# ProPrj_hid-remapper-v2_2026-05-31.net
KiCad netlist of a schematic drawn in EasyEDA Pro
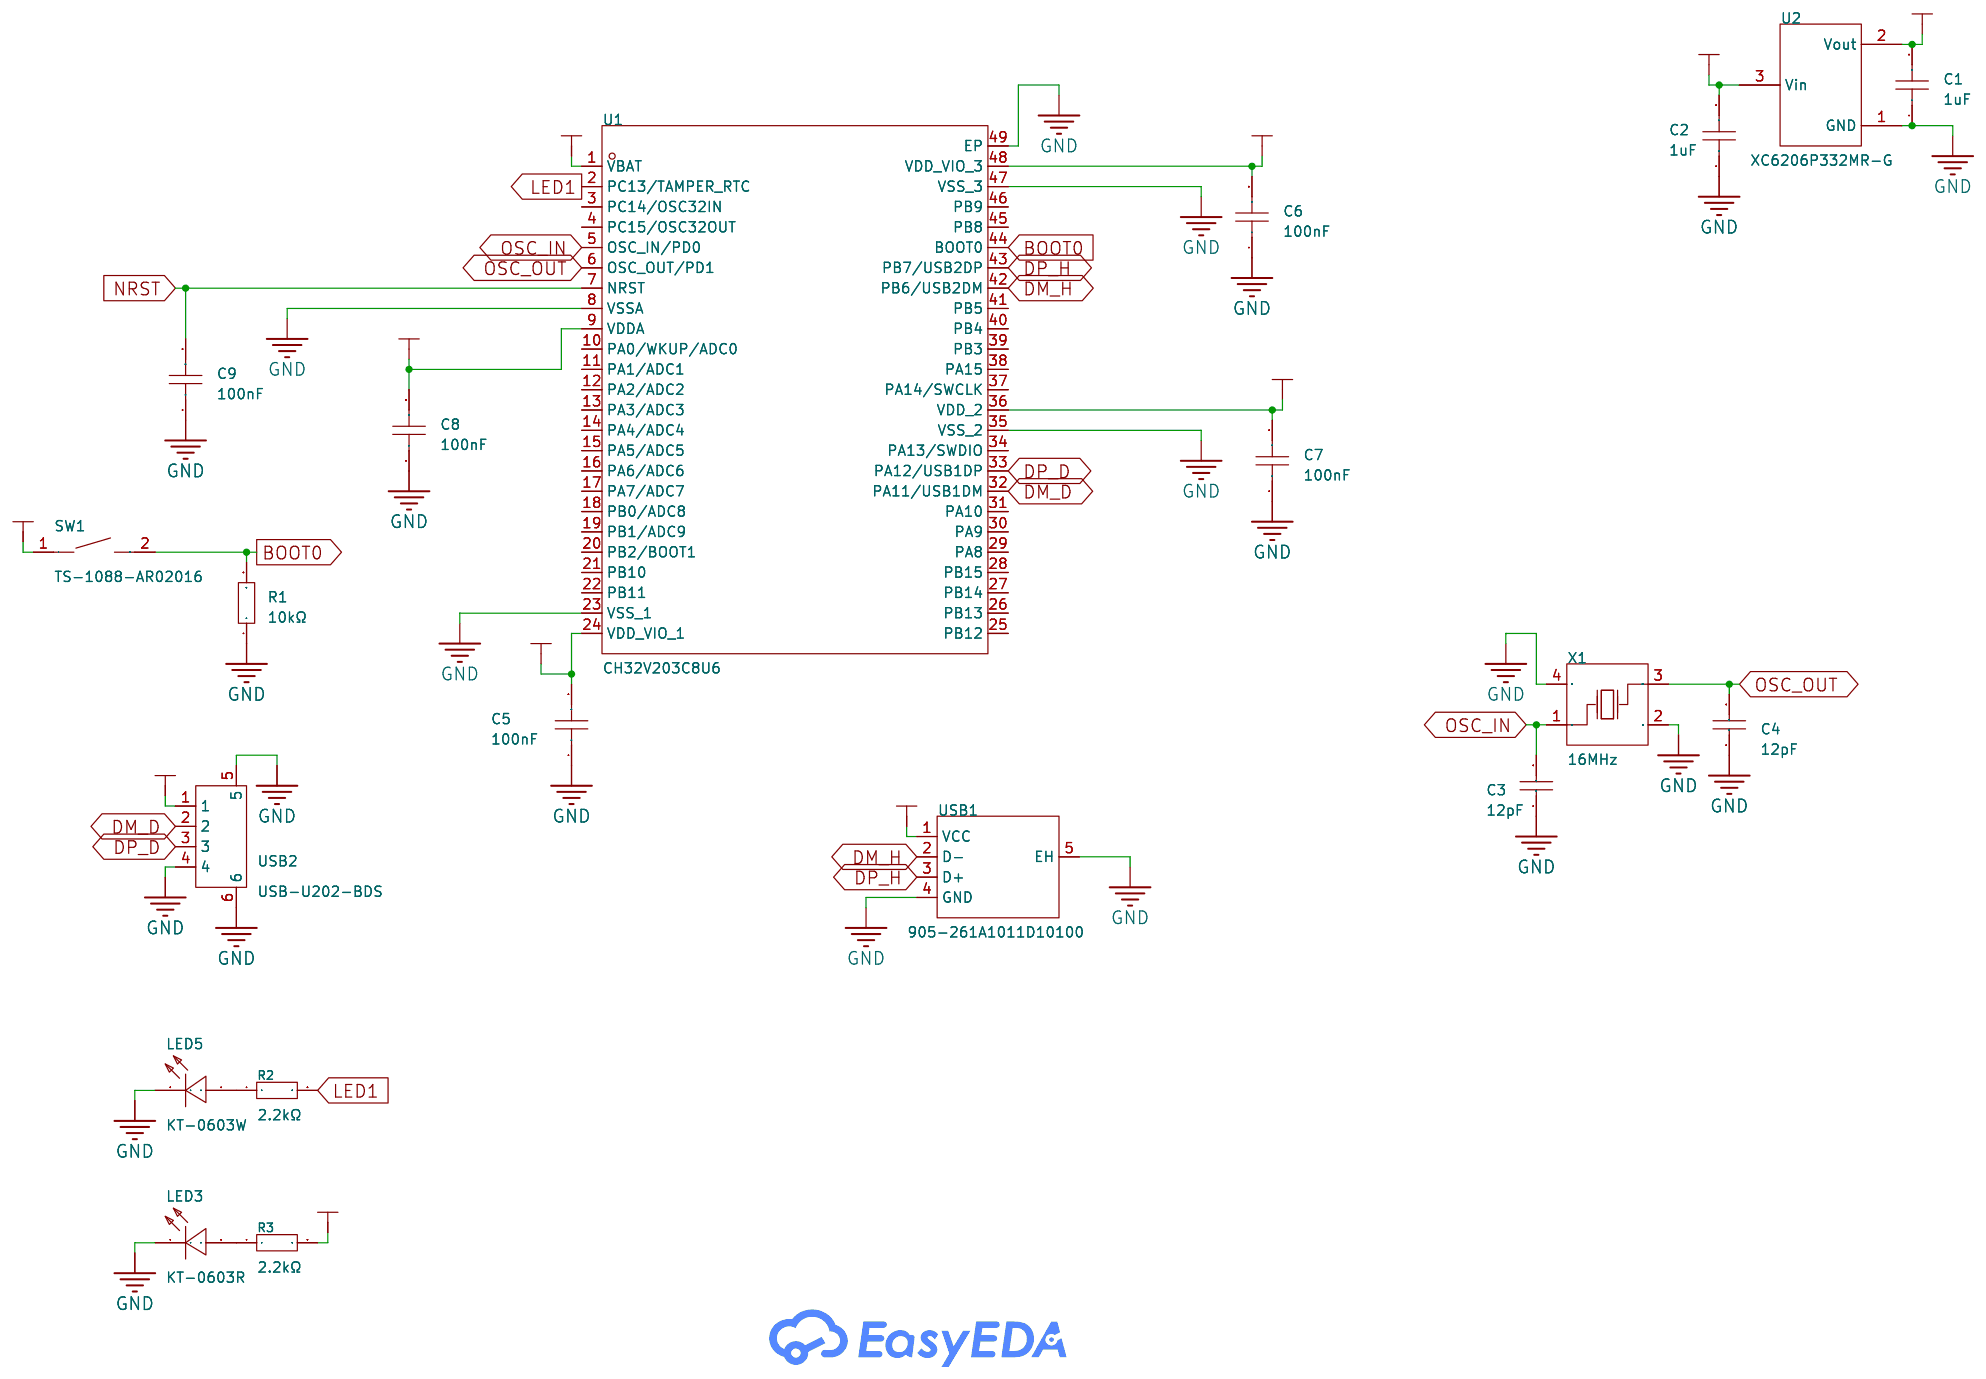
[diagram p0: schematic sheet]

(export (version "E")
  (design (tool "Eeschema 10.0.6"))
  (components
    (comp (ref "C1")
      (value "1uF")
      (footprint "easyedapro:C0402")
      (description "Capacitance:1uF Tolerance:±10% Tolerance:±10% Voltage Rating:25V Temperature Coefficient:X5R")
      (fields
        (field (name "Manufacturer Part") "CL05A105KA5NQNC")
        (field (name "Manufacturer") "SAMSUNG(三星)")
      )
      (libsource (lib "easyedapro") (part "CL05A105KA5NQNC"))
    )
    (comp (ref "C2")
      (value "1uF")
      (footprint "easyedapro:C0402")
      (description "Capacitance:1uF Tolerance:±10% Tolerance:±10% Voltage Rating:25V Temperature Coefficient:X5R")
      (fields
        (field (name "Manufacturer Part") "CL05A105KA5NQNC")
        (field (name "Manufacturer") "SAMSUNG(三星)")
      )
      (libsource (lib "easyedapro") (part "CL05A105KA5NQNC"))
    )
    (comp (ref "C3")
      (value "12pF")
      (footprint "easyedapro:C0402")
      (description "Capacitance:12pF Tolerance:±5% Tolerance:±5% Voltage Rating:50V Temperature Coefficient:C0G")
      (fields (field (name "Manufacturer Part") "0402CG120J500NT") (field (name "Manufacturer") "FH(风华)"))
      (libsource (lib "easyedapro") (part "0402CG120J500NT"))
    )
    (comp (ref "C4")
      (value "12pF")
      (footprint "easyedapro:C0402")
      (description "Capacitance:12pF Tolerance:±5% Tolerance:±5% Voltage Rating:50V Temperature Coefficient:C0G")
      (fields (field (name "Manufacturer Part") "0402CG120J500NT") (field (name "Manufacturer") "FH(风华)"))
      (libsource (lib "easyedapro") (part "0402CG120J500NT"))
    )
    (comp (ref "C5")
      (value "100nF")
      (footprint "easyedapro:C0402")
      (description "Capacitance:100nF Tolerance:±10% Tolerance:±10% Voltage Rating:16V Temperature Coefficient:X7R")
      (fields
        (field (name "Manufacturer Part") "CL05B104KO5NNNC")
        (field (name "Manufacturer") "SAMSUNG(三星)")
      )
      (libsource (lib "easyedapro") (part "CL05B104KO5NNNC"))
    )
    (comp (ref "C6")
      (value "100nF")
      (footprint "easyedapro:C0402")
      (description "Capacitance:100nF Tolerance:±10% Tolerance:±10% Voltage Rating:16V Temperature Coefficient:X7R")
      (fields
        (field (name "Manufacturer Part") "CL05B104KO5NNNC")
        (field (name "Manufacturer") "SAMSUNG(三星)")
      )
      (libsource (lib "easyedapro") (part "CL05B104KO5NNNC"))
    )
    (comp (ref "C7")
      (value "100nF")
      (footprint "easyedapro:C0402")
      (description "Capacitance:100nF Tolerance:±10% Tolerance:±10% Voltage Rating:16V Temperature Coefficient:X7R")
      (fields
        (field (name "Manufacturer Part") "CL05B104KO5NNNC")
        (field (name "Manufacturer") "SAMSUNG(三星)")
      )
      (libsource (lib "easyedapro") (part "CL05B104KO5NNNC"))
    )
    (comp (ref "C8")
      (value "100nF")
      (footprint "easyedapro:C0402")
      (description "Capacitance:100nF Tolerance:±10% Tolerance:±10% Voltage Rating:16V Temperature Coefficient:X7R")
      (fields
        (field (name "Manufacturer Part") "CL05B104KO5NNNC")
        (field (name "Manufacturer") "SAMSUNG(三星)")
      )
      (libsource (lib "easyedapro") (part "CL05B104KO5NNNC"))
    )
    (comp (ref "C9")
      (value "100nF")
      (footprint "easyedapro:C0402")
      (description "Capacitance:100nF Tolerance:±10% Tolerance:±10% Voltage Rating:16V Temperature Coefficient:X7R")
      (fields
        (field (name "Manufacturer Part") "CL05B104KO5NNNC")
        (field (name "Manufacturer") "SAMSUNG(三星)")
      )
      (libsource (lib "easyedapro") (part "CL05B104KO5NNNC"))
    )
    (comp (ref "LED3")
      (value "KT-0603R")
      (footprint "easyedapro:LED0603-RD")
      (fields (field (name "Manufacturer") "KENTO"))
      (libsource (lib "easyedapro") (part "KT-0603R"))
    )
    (comp (ref "LED5")
      (value "KT-0603W")
      (footprint "easyedapro:LED0603-R-RD_WHITE")
      (fields (field (name "Manufacturer") "KENTO"))
      (libsource (lib "easyedapro") (part "0603White light_C2290"))
    )
    (comp (ref "R1")
      (value "10kΩ")
      (footprint "easyedapro:R0402")
      (fields
        (field (name "Manufacturer Part") "0402WGF1002TCE")
        (field (name "Manufacturer") "UNI-ROYAL(厚声)")
      )
      (libsource (lib "easyedapro") (part "0402WGF1002TCE"))
    )
    (comp (ref "R2")
      (value "2.2kΩ")
      (footprint "easyedapro:R0402")
      (fields
        (field (name "Manufacturer Part") "0402WGF2201TCE")
        (field (name "Manufacturer") "UNI-ROYAL(厚声)")
      )
      (libsource (lib "easyedapro") (part "0402WGF2201TCE"))
    )
    (comp (ref "R3")
      (value "2.2kΩ")
      (footprint "easyedapro:R0402")
      (fields
        (field (name "Manufacturer Part") "0402WGF2201TCE")
        (field (name "Manufacturer") "UNI-ROYAL(厚声)")
      )
      (libsource (lib "easyedapro") (part "0402WGF2201TCE"))
    )
    (comp (ref "SW1")
      (value "TS-1088-AR02016")
      (footprint "easyedapro:SW-SMD_L3.9-W3.0-P4.45")
      (fields (field (name "Manufacturer") "XUNPU(讯普)"))
      (libsource (lib "easyedapro") (part "TS-1088-AR02016"))
    )
    (comp (ref "U1")
      (value "CH32V203C8U6")
      (footprint "easyedapro:TQFN-48_L7.0-W7.0-P0.50-BL-EP5.5")
      (fields (field (name "Manufacturer") "WCH(南京沁恒)"))
      (libsource (lib "easyedapro") (part "CH32V203C8U6"))
    )
    (comp (ref "U2")
      (value "XC6206P332MR-G")
      (footprint "easyedapro:SOT-23-3_L2.9-W1.6-P1.90-LS2.8-BR")
      (fields (field (name "Manufacturer") "TOREX(特瑞仕)"))
      (libsource (lib "easyedapro") (part "XC6206P332MR"))
    )
    (comp (ref "USB1")
      (value "905-261A1011D10100")
      (footprint "easyedapro:USB-A-TH_JTJ-USB-AF-13")
      (fields (field (name "Manufacturer") "精拓金"))
      (libsource (lib "easyedapro") (part "C42614"))
    )
    (comp (ref "USB2")
      (value "USB-U202-BDS")
      (footprint "easyedapro:USB_USB-U202-BDS")
      (fields (field (name "Manufacturer") "HANBO(汉博)"))
      (libsource (lib "easyedapro") (part "USB-U202-BDS"))
    )
    (comp (ref "X1")
      (value "16MHz")
      (footprint "easyedapro:OSC-SMD_4P-L3.2-W2.5-BL")
      (fields (field (name "Manufacturer Part") "X322516MLB4SI") (field (name "Manufacturer") "YXC(扬兴晶振)"))
      (libsource (lib "easyedapro") (part "X322516MLB4SI"))
    )
  )
  (nets
    (net (code "1") (name "3V3") (class "Default")
      (node (ref "C1") (pin "2") (pinfunction "2_2") (pintype "unspecified"))
      (node (ref "C5") (pin "2") (pinfunction "2_2") (pintype "unspecified"))
      (node (ref "C6") (pin "2") (pinfunction "2_2") (pintype "unspecified"))
      (node (ref "C7") (pin "2") (pinfunction "2_2") (pintype "unspecified"))
      (node (ref "C8") (pin "2") (pinfunction "2_2") (pintype "unspecified"))
      (node (ref "R3") (pin "2") (pinfunction "2_2") (pintype "input"))
      (node (ref "SW1") (pin "1") (pinfunction "1_1") (pintype "unspecified"))
      (node (ref "U1") (pin "1") (pinfunction "VBAT_1") (pintype "unspecified"))
      (node (ref "U1") (pin "24") (pinfunction "VDD_VIO_1_24") (pintype "unspecified"))
      (node (ref "U1") (pin "36") (pinfunction "VDD_2_36") (pintype "unspecified"))
      (node (ref "U1") (pin "48") (pinfunction "VDD_VIO_3_48") (pintype "unspecified"))
      (node (ref "U1") (pin "9") (pinfunction "VDDA_9") (pintype "unspecified"))
      (node (ref "U2") (pin "2") (pinfunction "Vout_2") (pintype "unspecified"))
    )
    (net (code "2") (name "BOOT0") (class "Default")
      (node (ref "R1") (pin "2") (pinfunction "2_2") (pintype "input"))
      (node (ref "SW1") (pin "2") (pinfunction "2_2") (pintype "unspecified"))
      (node (ref "U1") (pin "44") (pinfunction "BOOT0_44") (pintype "unspecified"))
    )
    (net (code "3") (name "DM_D") (class "Default")
      (node (ref "U1") (pin "32") (pinfunction "PA11/USB1DM_32") (pintype "unspecified"))
      (node (ref "USB2") (pin "2") (pinfunction "2_2") (pintype "unspecified"))
    )
    (net (code "4") (name "DM_H") (class "Default")
      (node (ref "U1") (pin "42") (pinfunction "PB6/USB2DM_42") (pintype "unspecified"))
      (node (ref "USB1") (pin "2") (pinfunction "D-_2") (pintype "input"))
    )
    (net (code "5") (name "DP_D") (class "Default")
      (node (ref "U1") (pin "33") (pinfunction "PA12/USB1DP_33") (pintype "unspecified"))
      (node (ref "USB2") (pin "3") (pinfunction "3_3") (pintype "unspecified"))
    )
    (net (code "6") (name "DP_H") (class "Default")
      (node (ref "U1") (pin "43") (pinfunction "PB7/USB2DP_43") (pintype "unspecified"))
      (node (ref "USB1") (pin "3") (pinfunction "D+_3") (pintype "input"))
    )
    (net (code "7") (name "GND") (class "Default")
      (node (ref "C1") (pin "1") (pinfunction "1_1") (pintype "unspecified"))
      (node (ref "C2") (pin "1") (pinfunction "1_1") (pintype "unspecified"))
      (node (ref "C3") (pin "1") (pinfunction "1_1") (pintype "input"))
      (node (ref "C4") (pin "1") (pinfunction "1_1") (pintype "input"))
      (node (ref "C5") (pin "1") (pinfunction "1_1") (pintype "unspecified"))
      (node (ref "C6") (pin "1") (pinfunction "1_1") (pintype "unspecified"))
      (node (ref "C7") (pin "1") (pinfunction "1_1") (pintype "unspecified"))
      (node (ref "C8") (pin "1") (pinfunction "1_1") (pintype "unspecified"))
      (node (ref "C9") (pin "1") (pinfunction "1_1") (pintype "unspecified"))
      (node (ref "LED3") (pin "1") (pinfunction "K_1") (pintype "unspecified"))
      (node (ref "LED5") (pin "2") (pinfunction "K_2") (pintype "unspecified"))
      (node (ref "R1") (pin "1") (pinfunction "1_1") (pintype "input"))
      (node (ref "U1") (pin "23") (pinfunction "VSS_1_23") (pintype "unspecified"))
      (node (ref "U1") (pin "35") (pinfunction "VSS_2_35") (pintype "unspecified"))
      (node (ref "U1") (pin "47") (pinfunction "VSS_3_47") (pintype "unspecified"))
      (node (ref "U1") (pin "49") (pinfunction "EP_49") (pintype "unspecified"))
      (node (ref "U1") (pin "8") (pinfunction "VSSA_8") (pintype "unspecified"))
      (node (ref "U2") (pin "1") (pinfunction "GND_1") (pintype "unspecified"))
      (node (ref "USB1") (pin "4") (pinfunction "GND_4") (pintype "input"))
      (node (ref "USB1") (pin "5") (pinfunction "EH_5") (pintype "unspecified"))
      (node (ref "USB2") (pin "4") (pinfunction "4_4") (pintype "unspecified"))
      (node (ref "USB2") (pin "5") (pinfunction "5_5") (pintype "unspecified"))
      (node (ref "USB2") (pin "6") (pinfunction "6_6") (pintype "unspecified"))
      (node (ref "X1") (pin "2") (pinfunction "GND_2") (pintype "unspecified"))
      (node (ref "X1") (pin "4") (pinfunction "GND_4") (pintype "unspecified"))
    )
    (net (code "8") (name "LED1") (class "Default")
      (node (ref "R2") (pin "2") (pinfunction "2_2") (pintype "input"))
      (node (ref "U1") (pin "2") (pinfunction "PC13/TAMPER_RTC_2") (pintype "unspecified"))
    )
    (net (code "9") (name "NRST") (class "Default")
      (node (ref "C9") (pin "2") (pinfunction "2_2") (pintype "unspecified"))
      (node (ref "U1") (pin "7") (pinfunction "NRST_7") (pintype "unspecified"))
    )
    (net (code "10") (name "Net-(LED3-A)") (class "Default")
      (node (ref "LED3") (pin "2") (pinfunction "A_2") (pintype "unspecified"))
      (node (ref "R3") (pin "1") (pinfunction "1_1") (pintype "input"))
    )
    (net (code "11") (name "Net-(LED5-A)") (class "Default")
      (node (ref "LED5") (pin "1") (pinfunction "A_1") (pintype "unspecified"))
      (node (ref "R2") (pin "1") (pinfunction "1_1") (pintype "input"))
    )
    (net (code "12") (name "OSC_IN") (class "Default")
      (node (ref "C3") (pin "2") (pinfunction "2_2") (pintype "input"))
      (node (ref "U1") (pin "5") (pinfunction "OSC_IN/PD0_5") (pintype "unspecified"))
      (node (ref "X1") (pin "1") (pinfunction "OSC1_1") (pintype "unspecified"))
    )
    (net (code "13") (name "OSC_OUT") (class "Default")
      (node (ref "C4") (pin "2") (pinfunction "2_2") (pintype "input"))
      (node (ref "U1") (pin "6") (pinfunction "OSC_OUT/PD1_6") (pintype "unspecified"))
      (node (ref "X1") (pin "3") (pinfunction "OSC2_3") (pintype "unspecified"))
    )
    (net (code "14") (name "VBUS") (class "Default")
      (node (ref "C2") (pin "2") (pinfunction "2_2") (pintype "unspecified"))
      (node (ref "U2") (pin "3") (pinfunction "Vin_3") (pintype "unspecified"))
      (node (ref "USB1") (pin "1") (pinfunction "VCC_1") (pintype "input"))
      (node (ref "USB2") (pin "1") (pinfunction "1_1") (pintype "unspecified"))
    )
    (net (code "15") (name "unconnected-(U1-PA0{slash}WKUP{slash}ADC0-Pad10)") (class "Default")
      (node (ref "U1") (pin "10") (pinfunction "PA0/WKUP/ADC0_10") (pintype "unspecified"))
    )
    (net (code "16") (name "unconnected-(U1-PA1{slash}ADC1-Pad11)") (class "Default")
      (node (ref "U1") (pin "11") (pinfunction "PA1/ADC1_11") (pintype "unspecified"))
    )
    (net (code "17") (name "unconnected-(U1-PA2{slash}ADC2-Pad12)") (class "Default")
      (node (ref "U1") (pin "12") (pinfunction "PA2/ADC2_12") (pintype "unspecified"))
    )
    (net (code "18") (name "unconnected-(U1-PA3{slash}ADC3-Pad13)") (class "Default")
      (node (ref "U1") (pin "13") (pinfunction "PA3/ADC3_13") (pintype "unspecified"))
    )
    (net (code "19") (name "unconnected-(U1-PA4{slash}ADC4-Pad14)") (class "Default")
      (node (ref "U1") (pin "14") (pinfunction "PA4/ADC4_14") (pintype "unspecified"))
    )
    (net (code "20") (name "unconnected-(U1-PA5{slash}ADC5-Pad15)") (class "Default")
      (node (ref "U1") (pin "15") (pinfunction "PA5/ADC5_15") (pintype "unspecified"))
    )
    (net (code "21") (name "unconnected-(U1-PA6{slash}ADC6-Pad16)") (class "Default")
      (node (ref "U1") (pin "16") (pinfunction "PA6/ADC6_16") (pintype "unspecified"))
    )
    (net (code "22") (name "unconnected-(U1-PA7{slash}ADC7-Pad17)") (class "Default")
      (node (ref "U1") (pin "17") (pinfunction "PA7/ADC7_17") (pintype "unspecified"))
    )
    (net (code "23") (name "unconnected-(U1-PA8-Pad29)") (class "Default")
      (node (ref "U1") (pin "29") (pinfunction "PA8_29") (pintype "unspecified"))
    )
    (net (code "24") (name "unconnected-(U1-PA9-Pad30)") (class "Default")
      (node (ref "U1") (pin "30") (pinfunction "PA9_30") (pintype "unspecified"))
    )
    (net (code "25") (name "unconnected-(U1-PA10-Pad31)") (class "Default")
      (node (ref "U1") (pin "31") (pinfunction "PA10_31") (pintype "unspecified"))
    )
    (net (code "26") (name "unconnected-(U1-PA13{slash}SWDIO-Pad34)") (class "Default")
      (node (ref "U1") (pin "34") (pinfunction "PA13/SWDIO_34") (pintype "unspecified"))
    )
    (net (code "27") (name "unconnected-(U1-PA14{slash}SWCLK-Pad37)") (class "Default")
      (node (ref "U1") (pin "37") (pinfunction "PA14/SWCLK_37") (pintype "unspecified"))
    )
    (net (code "28") (name "unconnected-(U1-PA15-Pad38)") (class "Default")
      (node (ref "U1") (pin "38") (pinfunction "PA15_38") (pintype "unspecified"))
    )
    (net (code "29") (name "unconnected-(U1-PB0{slash}ADC8-Pad18)") (class "Default")
      (node (ref "U1") (pin "18") (pinfunction "PB0/ADC8_18") (pintype "unspecified"))
    )
    (net (code "30") (name "unconnected-(U1-PB1{slash}ADC9-Pad19)") (class "Default")
      (node (ref "U1") (pin "19") (pinfunction "PB1/ADC9_19") (pintype "unspecified"))
    )
    (net (code "31") (name "unconnected-(U1-PB2{slash}BOOT1-Pad20)") (class "Default")
      (node (ref "U1") (pin "20") (pinfunction "PB2/BOOT1_20") (pintype "unspecified"))
    )
    (net (code "32") (name "unconnected-(U1-PB3-Pad39)") (class "Default")
      (node (ref "U1") (pin "39") (pinfunction "PB3_39") (pintype "unspecified"))
    )
    (net (code "33") (name "unconnected-(U1-PB4-Pad40)") (class "Default")
      (node (ref "U1") (pin "40") (pinfunction "PB4_40") (pintype "unspecified"))
    )
    (net (code "34") (name "unconnected-(U1-PB5-Pad41)") (class "Default")
      (node (ref "U1") (pin "41") (pinfunction "PB5_41") (pintype "unspecified"))
    )
    (net (code "35") (name "unconnected-(U1-PB8-Pad45)") (class "Default")
      (node (ref "U1") (pin "45") (pinfunction "PB8_45") (pintype "unspecified"))
    )
    (net (code "36") (name "unconnected-(U1-PB9-Pad46)") (class "Default")
      (node (ref "U1") (pin "46") (pinfunction "PB9_46") (pintype "unspecified"))
    )
    (net (code "37") (name "unconnected-(U1-PB10-Pad21)") (class "Default")
      (node (ref "U1") (pin "21") (pinfunction "PB10_21") (pintype "unspecified"))
    )
    (net (code "38") (name "unconnected-(U1-PB11-Pad22)") (class "Default")
      (node (ref "U1") (pin "22") (pinfunction "PB11_22") (pintype "unspecified"))
    )
    (net (code "39") (name "unconnected-(U1-PB12-Pad25)") (class "Default")
      (node (ref "U1") (pin "25") (pinfunction "PB12_25") (pintype "unspecified"))
    )
    (net (code "40") (name "unconnected-(U1-PB13-Pad26)") (class "Default")
      (node (ref "U1") (pin "26") (pinfunction "PB13_26") (pintype "unspecified"))
    )
    (net (code "41") (name "unconnected-(U1-PB14-Pad27)") (class "Default")
      (node (ref "U1") (pin "27") (pinfunction "PB14_27") (pintype "unspecified"))
    )
    (net (code "42") (name "unconnected-(U1-PB15-Pad28)") (class "Default")
      (node (ref "U1") (pin "28") (pinfunction "PB15_28") (pintype "unspecified"))
    )
    (net (code "43") (name "unconnected-(U1-PC14{slash}OSC32IN-Pad3)") (class "Default")
      (node (ref "U1") (pin "3") (pinfunction "PC14/OSC32IN_3") (pintype "unspecified"))
    )
    (net (code "44") (name "unconnected-(U1-PC15{slash}OSC32OUT-Pad4)") (class "Default")
      (node (ref "U1") (pin "4") (pinfunction "PC15/OSC32OUT_4") (pintype "unspecified"))
    )
  )
)
